# Omnicron_PCB.net
KiCad netlist of a schematic drawn in Altium Designer
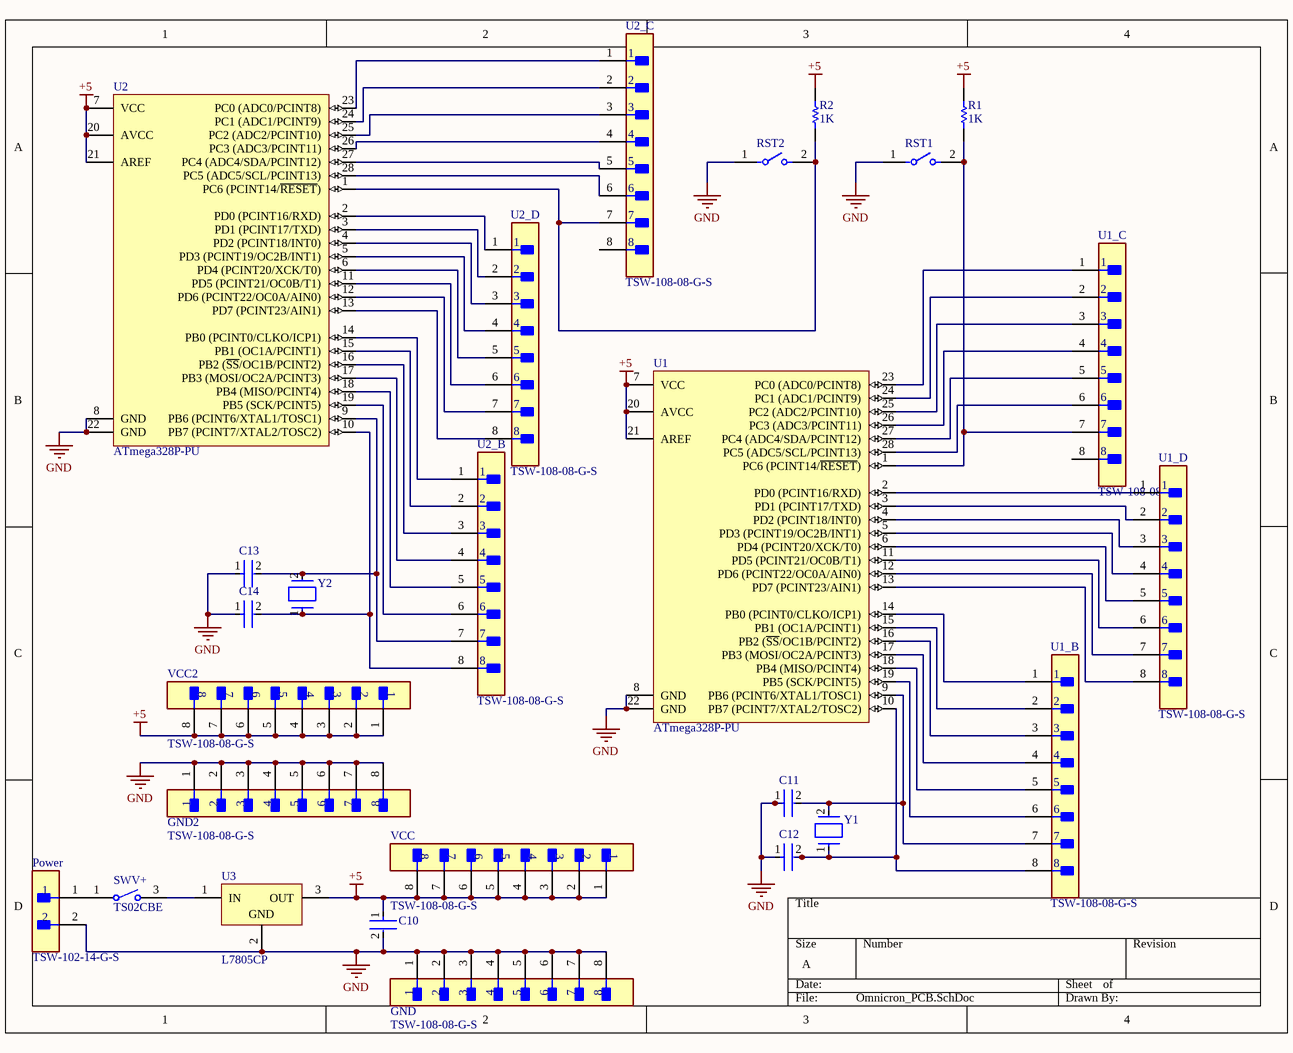
[diagram p0: Omnicron_PCB.SchDoc]

(export (version "E")
  (design (tool "Eeschema 10.0.6"))
  (components
    (comp (ref "C10")
      (value "~")
      (footprint "FP-561R10TSQ30-MFG")
      (description "CAP CER 30PF 1KV U2J RADIAL")
      (fields (field (name "TOLERANCE") "10%") (field (name "VOLTAGE") "1kV"))
      (libsource (lib "Altium Content Vault") (part "b4654b650e69147ec39a6b967a45e02"))
    )
    (comp (ref "C11")
      (value "~")
      (footprint "FP-561R10TSQ30-MFG")
      (description "CAP CER 30PF 1KV U2J RADIAL")
      (fields (field (name "TOLERANCE") "10%") (field (name "VOLTAGE") "1kV"))
      (libsource (lib "Altium Content Vault") (part "b4654b650e69147ec39a6b967a45e02"))
    )
    (comp (ref "C12")
      (value "~")
      (footprint "FP-561R10TSQ30-MFG")
      (description "CAP CER 30PF 1KV U2J RADIAL")
      (fields (field (name "TOLERANCE") "10%") (field (name "VOLTAGE") "1kV"))
      (libsource (lib "Altium Content Vault") (part "b4654b650e69147ec39a6b967a45e02"))
    )
    (comp (ref "C13")
      (value "~")
      (footprint "FP-561R10TSQ30-MFG")
      (description "CAP CER 30PF 1KV U2J RADIAL")
      (fields (field (name "TOLERANCE") "10%") (field (name "VOLTAGE") "1kV"))
      (libsource (lib "Altium Content Vault") (part "b4654b650e69147ec39a6b967a45e02"))
    )
    (comp (ref "C14")
      (value "~")
      (footprint "FP-561R10TSQ30-MFG")
      (description "CAP CER 30PF 1KV U2J RADIAL")
      (fields (field (name "TOLERANCE") "10%") (field (name "VOLTAGE") "1kV"))
      (libsource (lib "Altium Content Vault") (part "b4654b650e69147ec39a6b967a45e02"))
    )
    (comp (ref "GND")
      (value "TSW-108-08-G-S")
      (footprint "FP-TSW-108-08-G-S-MFG")
      (description "CONN HEADER VERT 8POS 2.54MM")
      (fields
        (field (name "MANUFACTURER") "Samtec")
        (field (name "OCTOPART") "https://octopart.com/tsw-108-08-g-s-samtec-272653")
      )
      (libsource (lib "") (part "99ec2b232beb5d2356d4d77f6a047f0_1"))
    )
    (comp (ref "GND2")
      (value "TSW-108-08-G-S")
      (footprint "FP-TSW-108-08-G-S-MFG")
      (description "CONN HEADER VERT 8POS 2.54MM")
      (fields
        (field (name "MANUFACTURER") "Samtec")
        (field (name "OCTOPART") "https://octopart.com/tsw-108-08-g-s-samtec-272653")
      )
      (libsource (lib "") (part "99ec2b232beb5d2356d4d77f6a047f0_1"))
    )
    (comp (ref "Power")
      (value "TSW-102-14-G-S")
      (footprint "FP-TSW-102-14-G-S-MFG")
      (description "CONN HEADER VERT 2POS 2.54MM")
      (libsource (lib "Altium Content Vault") (part "88c1139f9d239099ffebecbe3f7647a"))
    )
    (comp (ref "R1")
      (value "1K")
      (footprint "RESA60-630X240")
      (description "Axial Resistor, 1 KOhm, +/- 1%, 250 mW, -55 to 155 degC, 2-Pin THD, RoHS, Bulk")
      (fields (field (name "TOLERANCE") "1%"))
      (libsource (lib "Altium Content Vault") (part "RES-2"))
    )
    (comp (ref "R2")
      (value "1K")
      (footprint "RESA60-630X240")
      (description "Axial Resistor, 1 KOhm, +/- 1%, 250 mW, -55 to 155 degC, 2-Pin THD, RoHS, Bulk")
      (fields (field (name "TOLERANCE") "1%"))
      (libsource (lib "Altium Content Vault") (part "RES-2"))
    )
    (comp (ref "RST1")
      (value "~")
      (footprint "FP-FSM2JART-MFG")
      (description "SWITCH TACTILE SPST-NO 0.05A 12V")
      (libsource (lib "Altium Content Vault") (part "bb27bde45df87f1f469753f287ef5ae"))
    )
    (comp (ref "RST2")
      (value "~")
      (footprint "FP-FSM2JART-MFG")
      (description "SWITCH TACTILE SPST-NO 0.05A 12V")
      (libsource (lib "Altium Content Vault") (part "bb27bde45df87f1f469753f287ef5ae"))
    )
    (comp (ref "SWV+")
      (value "TS02CBE")
      (footprint "CKCP-TS02CBE_V")
      (description "Tiny Slide Switch, SPST, 20 V, -30 to 85 degC, 2-Pin THD, RoHS, Bulk")
      (fields (field (name "MANUFACTURER") "C&K Components"))
      (libsource (lib "Altium Content Vault") (part "SW-SPST-2"))
    )
    (comp (ref "U1")
      (value "ATmega328P-PU")
      (footprint "28P3")
      (libsource (lib "Altium Content Vault") (part "MC-8B-ATM48-IL28"))
    )
    (comp (ref "U1_B")
      (value "TSW-108-08-G-S")
      (footprint "FP-TSW-108-08-G-S-MFG")
      (description "CONN HEADER VERT 8POS 2.54MM")
      (fields
        (field (name "MANUFACTURER") "Samtec")
        (field (name "OCTOPART") "https://octopart.com/tsw-108-08-g-s-samtec-272653")
      )
      (libsource (lib "Altium Content Vault") (part "99ec2b232beb5d2356d4d77f6a047f0"))
    )
    (comp (ref "U1_C")
      (value "TSW-108-08-G-S")
      (footprint "FP-TSW-108-08-G-S-MFG")
      (description "CONN HEADER VERT 8POS 2.54MM")
      (fields
        (field (name "MANUFACTURER") "Samtec")
        (field (name "OCTOPART") "https://octopart.com/tsw-108-08-g-s-samtec-272653")
      )
      (libsource (lib "Altium Content Vault") (part "99ec2b232beb5d2356d4d77f6a047f0"))
    )
    (comp (ref "U1_D")
      (value "TSW-108-08-G-S")
      (footprint "FP-TSW-108-08-G-S-MFG")
      (description "CONN HEADER VERT 8POS 2.54MM")
      (fields
        (field (name "MANUFACTURER") "Samtec")
        (field (name "OCTOPART") "https://octopart.com/tsw-108-08-g-s-samtec-272653")
      )
      (libsource (lib "Altium Content Vault") (part "99ec2b232beb5d2356d4d77f6a047f0"))
    )
    (comp (ref "U2")
      (value "ATmega328P-PU")
      (footprint "28P3")
      (libsource (lib "Altium Content Vault") (part "MC-8B-ATM48-IL28"))
    )
    (comp (ref "U2_B")
      (value "TSW-108-08-G-S")
      (footprint "FP-TSW-108-08-G-S-MFG")
      (description "CONN HEADER VERT 8POS 2.54MM")
      (fields
        (field (name "MANUFACTURER") "Samtec")
        (field (name "OCTOPART") "https://octopart.com/tsw-108-08-g-s-samtec-272653")
      )
      (libsource (lib "Altium Content Vault") (part "99ec2b232beb5d2356d4d77f6a047f0"))
    )
    (comp (ref "U2_C")
      (value "TSW-108-08-G-S")
      (footprint "FP-TSW-108-08-G-S-MFG")
      (description "CONN HEADER VERT 8POS 2.54MM")
      (fields
        (field (name "MANUFACTURER") "Samtec")
        (field (name "OCTOPART") "https://octopart.com/tsw-108-08-g-s-samtec-272653")
      )
      (libsource (lib "Altium Content Vault") (part "99ec2b232beb5d2356d4d77f6a047f0"))
    )
    (comp (ref "U2_D")
      (value "TSW-108-08-G-S")
      (footprint "FP-TSW-108-08-G-S-MFG")
      (description "CONN HEADER VERT 8POS 2.54MM")
      (fields
        (field (name "MANUFACTURER") "Samtec")
        (field (name "OCTOPART") "https://octopart.com/tsw-108-08-g-s-samtec-272653")
      )
      (libsource (lib "Altium Content Vault") (part "99ec2b232beb5d2356d4d77f6a047f0"))
    )
    (comp (ref "U3")
      (value "L7805CP")
      (footprint "TO220FP")
      (description "Positive Voltage Regulator, 5V, 3-Pin TO-220FP")
      (libsource (lib "Altium Content Vault") (part "PM-REG-L4940-SIL3"))
    )
    (comp (ref "VCC")
      (value "TSW-108-08-G-S")
      (footprint "FP-TSW-108-08-G-S-MFG")
      (description "CONN HEADER VERT 8POS 2.54MM")
      (fields
        (field (name "MANUFACTURER") "Samtec")
        (field (name "OCTOPART") "https://octopart.com/tsw-108-08-g-s-samtec-272653")
      )
      (libsource (lib "Altium Content Vault") (part "99ec2b232beb5d2356d4d77f6a047f0"))
    )
    (comp (ref "VCC2")
      (value "TSW-108-08-G-S")
      (footprint "FP-TSW-108-08-G-S-MFG")
      (description "CONN HEADER VERT 8POS 2.54MM")
      (fields
        (field (name "MANUFACTURER") "Samtec")
        (field (name "OCTOPART") "https://octopart.com/tsw-108-08-g-s-samtec-272653")
      )
      (libsource (lib "Altium Content Vault") (part "99ec2b232beb5d2356d4d77f6a047f0"))
    )
    (comp (ref "Y1")
      (value "~")
      (footprint "FP-ECS-80-20-4X-MFG")
      (fields (field (name "TOLERANCE") "0.003%"))
      (libsource (lib "Altium Content Vault") (part "c23a69dc6c9e2f18f2079038eb95dd1"))
    )
    (comp (ref "Y2")
      (value "~")
      (footprint "FP-ECS-80-20-4X-MFG")
      (fields (field (name "TOLERANCE") "0.003%"))
      (libsource (lib "Altium Content Vault") (part "c23a69dc6c9e2f18f2079038eb95dd1"))
    )
  )
  (nets
    (net (code "1") (name "+5") (class "Default")
      (node (ref "C10") (pin "1") (pinfunction "1_1") (pintype "passive"))
      (node (ref "R1") (pin "1") (pinfunction "1_1") (pintype "passive"))
      (node (ref "R2") (pin "1") (pinfunction "1_1") (pintype "passive"))
      (node (ref "U1") (pin "20") (pinfunction "AVCC_20") (pintype "power_in"))
      (node (ref "U1") (pin "21") (pinfunction "AREF_21") (pintype "power_in"))
      (node (ref "U1") (pin "7") (pinfunction "VCC_7") (pintype "power_in"))
      (node (ref "U2") (pin "20") (pinfunction "AVCC_20") (pintype "power_in"))
      (node (ref "U2") (pin "21") (pinfunction "AREF_21") (pintype "power_in"))
      (node (ref "U2") (pin "7") (pinfunction "VCC_7") (pintype "power_in"))
      (node (ref "U3") (pin "3") (pinfunction "OUT_3") (pintype "power_in"))
      (node (ref "VCC") (pin "1") (pinfunction "1_1") (pintype "passive"))
      (node (ref "VCC") (pin "2") (pinfunction "2_2") (pintype "passive"))
      (node (ref "VCC") (pin "3") (pinfunction "3_3") (pintype "passive"))
      (node (ref "VCC") (pin "4") (pinfunction "4_4") (pintype "passive"))
      (node (ref "VCC") (pin "5") (pinfunction "5_5") (pintype "passive"))
      (node (ref "VCC") (pin "6") (pinfunction "6_6") (pintype "passive"))
      (node (ref "VCC") (pin "7") (pinfunction "7_7") (pintype "passive"))
      (node (ref "VCC") (pin "8") (pinfunction "8_8") (pintype "passive"))
      (node (ref "VCC2") (pin "1") (pinfunction "1_1") (pintype "passive"))
      (node (ref "VCC2") (pin "2") (pinfunction "2_2") (pintype "passive"))
      (node (ref "VCC2") (pin "3") (pinfunction "3_3") (pintype "passive"))
      (node (ref "VCC2") (pin "4") (pinfunction "4_4") (pintype "passive"))
      (node (ref "VCC2") (pin "5") (pinfunction "5_5") (pintype "passive"))
      (node (ref "VCC2") (pin "6") (pinfunction "6_6") (pintype "passive"))
      (node (ref "VCC2") (pin "7") (pinfunction "7_7") (pintype "passive"))
      (node (ref "VCC2") (pin "8") (pinfunction "8_8") (pintype "passive"))
    )
    (net (code "2") (name "GND") (class "Default")
      (node (ref "C10") (pin "2") (pinfunction "2_2") (pintype "passive"))
      (node (ref "C11") (pin "1") (pinfunction "1_1") (pintype "passive"))
      (node (ref "C12") (pin "1") (pinfunction "1_1") (pintype "passive"))
      (node (ref "C13") (pin "1") (pinfunction "1_1") (pintype "passive"))
      (node (ref "C14") (pin "1") (pinfunction "1_1") (pintype "passive"))
      (node (ref "GND") (pin "1") (pinfunction "1_1") (pintype "passive"))
      (node (ref "GND") (pin "2") (pinfunction "2_2") (pintype "passive"))
      (node (ref "GND") (pin "3") (pinfunction "3_3") (pintype "passive"))
      (node (ref "GND") (pin "4") (pinfunction "4_4") (pintype "passive"))
      (node (ref "GND") (pin "5") (pinfunction "5_5") (pintype "passive"))
      (node (ref "GND") (pin "6") (pinfunction "6_6") (pintype "passive"))
      (node (ref "GND") (pin "7") (pinfunction "7_7") (pintype "passive"))
      (node (ref "GND") (pin "8") (pinfunction "8_8") (pintype "passive"))
      (node (ref "GND2") (pin "1") (pinfunction "1_1") (pintype "passive"))
      (node (ref "GND2") (pin "2") (pinfunction "2_2") (pintype "passive"))
      (node (ref "GND2") (pin "3") (pinfunction "3_3") (pintype "passive"))
      (node (ref "GND2") (pin "4") (pinfunction "4_4") (pintype "passive"))
      (node (ref "GND2") (pin "5") (pinfunction "5_5") (pintype "passive"))
      (node (ref "GND2") (pin "6") (pinfunction "6_6") (pintype "passive"))
      (node (ref "GND2") (pin "7") (pinfunction "7_7") (pintype "passive"))
      (node (ref "GND2") (pin "8") (pinfunction "8_8") (pintype "passive"))
      (node (ref "Power") (pin "2") (pinfunction "2_2") (pintype "passive"))
      (node (ref "RST1") (pin "1") (pinfunction "1_1") (pintype "passive"))
      (node (ref "RST2") (pin "1") (pinfunction "1_1") (pintype "passive"))
      (node (ref "U1") (pin "22") (pinfunction "GND_22") (pintype "power_in"))
      (node (ref "U1") (pin "8") (pinfunction "GND_8") (pintype "power_in"))
      (node (ref "U2") (pin "22") (pinfunction "GND_22") (pintype "power_in"))
      (node (ref "U2") (pin "8") (pinfunction "GND_8") (pintype "power_in"))
      (node (ref "U3") (pin "2") (pinfunction "GND_2") (pintype "power_in"))
    )
    (net (code "3") (name "Net-(Power-Pad1)") (class "Default")
      (node (ref "Power") (pin "1") (pinfunction "1_1") (pintype "passive"))
      (node (ref "SWV+") (pin "1") (pinfunction "1_1") (pintype "passive"))
    )
    (net (code "4") (name "Net-(U1-PB0_(PCINT0{slash}CLKO{slash}ICP1))") (class "Default")
      (node (ref "U1") (pin "14") (pinfunction "PB0_(PCINT0/CLKO/ICP1)_14") (pintype "bidirectional"))
      (node (ref "U1_B") (pin "1") (pinfunction "1_1") (pintype "passive"))
    )
    (net (code "5") (name "Net-(U1-PB1_(OC1A{slash}PCINT1))") (class "Default")
      (node (ref "U1") (pin "15") (pinfunction "PB1_(OC1A/PCINT1)_15") (pintype "bidirectional"))
      (node (ref "U1_B") (pin "2") (pinfunction "2_2") (pintype "passive"))
    )
    (net (code "6") (name "Net-(U1-PB2_(~{SS}{slash}OC1B{slash}PCINT2))") (class "Default")
      (node (ref "U1") (pin "16") (pinfunction "PB2_(~{SS}/OC1B/PCINT2)_16") (pintype "bidirectional"))
      (node (ref "U1_B") (pin "3") (pinfunction "3_3") (pintype "passive"))
    )
    (net (code "7") (name "Net-(U1-PB3_(MOSI{slash}OC2A{slash}PCINT3))") (class "Default")
      (node (ref "U1") (pin "17") (pinfunction "PB3_(MOSI/OC2A/PCINT3)_17") (pintype "bidirectional"))
      (node (ref "U1_B") (pin "4") (pinfunction "4_4") (pintype "passive"))
    )
    (net (code "8") (name "Net-(U1-PB4_(MISO{slash}PCINT4))") (class "Default")
      (node (ref "U1") (pin "18") (pinfunction "PB4_(MISO/PCINT4)_18") (pintype "bidirectional"))
      (node (ref "U1_B") (pin "5") (pinfunction "5_5") (pintype "passive"))
    )
    (net (code "9") (name "Net-(U1-PB5_(SCK{slash}PCINT5))") (class "Default")
      (node (ref "U1") (pin "19") (pinfunction "PB5_(SCK/PCINT5)_19") (pintype "bidirectional"))
      (node (ref "U1_B") (pin "6") (pinfunction "6_6") (pintype "passive"))
    )
    (net (code "10") (name "Net-(U1-PB6_(PCINT6{slash}XTAL1{slash}TOSC1))") (class "Default")
      (node (ref "C11") (pin "2") (pinfunction "2_2") (pintype "passive"))
      (node (ref "U1") (pin "9") (pinfunction "PB6_(PCINT6/XTAL1/TOSC1)_9") (pintype "bidirectional"))
      (node (ref "U1_B") (pin "7") (pinfunction "7_7") (pintype "passive"))
      (node (ref "Y1") (pin "2") (pinfunction "2_2") (pintype "passive"))
    )
    (net (code "11") (name "Net-(U1-PB7_(PCINT7{slash}XTAL2{slash}TOSC2))") (class "Default")
      (node (ref "C12") (pin "2") (pinfunction "2_2") (pintype "passive"))
      (node (ref "U1") (pin "10") (pinfunction "PB7_(PCINT7/XTAL2/TOSC2)_10") (pintype "bidirectional"))
      (node (ref "U1_B") (pin "8") (pinfunction "8_8") (pintype "passive"))
      (node (ref "Y1") (pin "1") (pinfunction "1_1") (pintype "passive"))
    )
    (net (code "12") (name "Net-(U1-PC0_(ADC0{slash}PCINT8))") (class "Default")
      (node (ref "U1") (pin "23") (pinfunction "PC0_(ADC0/PCINT8)_23") (pintype "bidirectional"))
      (node (ref "U1_C") (pin "1") (pinfunction "1_1") (pintype "passive"))
    )
    (net (code "13") (name "Net-(U1-PC1_(ADC1{slash}PCINT9))") (class "Default")
      (node (ref "U1") (pin "24") (pinfunction "PC1_(ADC1/PCINT9)_24") (pintype "bidirectional"))
      (node (ref "U1_C") (pin "2") (pinfunction "2_2") (pintype "passive"))
    )
    (net (code "14") (name "Net-(U1-PC2_(ADC2{slash}PCINT10))") (class "Default")
      (node (ref "U1") (pin "25") (pinfunction "PC2_(ADC2/PCINT10)_25") (pintype "bidirectional"))
      (node (ref "U1_C") (pin "3") (pinfunction "3_3") (pintype "passive"))
    )
    (net (code "15") (name "Net-(U1-PC3_(ADC3{slash}PCINT11))") (class "Default")
      (node (ref "U1") (pin "26") (pinfunction "PC3_(ADC3/PCINT11)_26") (pintype "bidirectional"))
      (node (ref "U1_C") (pin "4") (pinfunction "4_4") (pintype "passive"))
    )
    (net (code "16") (name "Net-(U1-PC4_(ADC4{slash}SDA{slash}PCINT12))") (class "Default")
      (node (ref "U1") (pin "27") (pinfunction "PC4_(ADC4/SDA/PCINT12)_27") (pintype "bidirectional"))
      (node (ref "U1_C") (pin "5") (pinfunction "5_5") (pintype "passive"))
    )
    (net (code "17") (name "Net-(U1-PC5_(ADC5{slash}SCL{slash}PCINT13))") (class "Default")
      (node (ref "U1") (pin "28") (pinfunction "PC5_(ADC5/SCL/PCINT13)_28") (pintype "bidirectional"))
      (node (ref "U1_C") (pin "6") (pinfunction "6_6") (pintype "passive"))
    )
    (net (code "18") (name "Net-(U1-PC6_(PCINT14{slash}~{RESET}))") (class "Default")
      (node (ref "R1") (pin "2") (pinfunction "2_2") (pintype "passive"))
      (node (ref "RST1") (pin "2") (pinfunction "2_2") (pintype "passive"))
      (node (ref "U1") (pin "1") (pinfunction "PC6_(PCINT14/~{RESET})_1") (pintype "bidirectional"))
      (node (ref "U1_C") (pin "7") (pinfunction "7_7") (pintype "passive"))
    )
    (net (code "19") (name "Net-(U1-PD0_(PCINT16{slash}RXD))") (class "Default")
      (node (ref "U1") (pin "2") (pinfunction "PD0_(PCINT16/RXD)_2") (pintype "bidirectional"))
      (node (ref "U1_D") (pin "1") (pinfunction "1_1") (pintype "passive"))
    )
    (net (code "20") (name "Net-(U1-PD1_(PCINT17{slash}TXD))") (class "Default")
      (node (ref "U1") (pin "3") (pinfunction "PD1_(PCINT17/TXD)_3") (pintype "bidirectional"))
      (node (ref "U1_D") (pin "2") (pinfunction "2_2") (pintype "passive"))
    )
    (net (code "21") (name "Net-(U1-PD2_(PCINT18{slash}INT0))") (class "Default")
      (node (ref "U1") (pin "4") (pinfunction "PD2_(PCINT18/INT0)_4") (pintype "bidirectional"))
      (node (ref "U1_D") (pin "3") (pinfunction "3_3") (pintype "passive"))
    )
    (net (code "22") (name "Net-(U1-PD3_(PCINT19{slash}OC2B{slash}INT1))") (class "Default")
      (node (ref "U1") (pin "5") (pinfunction "PD3_(PCINT19/OC2B/INT1)_5") (pintype "bidirectional"))
      (node (ref "U1_D") (pin "4") (pinfunction "4_4") (pintype "passive"))
    )
    (net (code "23") (name "Net-(U1-PD4_(PCINT20{slash}XCK{slash}T0))") (class "Default")
      (node (ref "U1") (pin "6") (pinfunction "PD4_(PCINT20/XCK/T0)_6") (pintype "bidirectional"))
      (node (ref "U1_D") (pin "5") (pinfunction "5_5") (pintype "passive"))
    )
    (net (code "24") (name "Net-(U1-PD5_(PCINT21{slash}OC0B{slash}T1))") (class "Default")
      (node (ref "U1") (pin "11") (pinfunction "PD5_(PCINT21/OC0B/T1)_11") (pintype "bidirectional"))
      (node (ref "U1_D") (pin "6") (pinfunction "6_6") (pintype "passive"))
    )
    (net (code "25") (name "Net-(U1-PD6_(PCINT22{slash}OC0A{slash}AIN0))") (class "Default")
      (node (ref "U1") (pin "12") (pinfunction "PD6_(PCINT22/OC0A/AIN0)_12") (pintype "bidirectional"))
      (node (ref "U1_D") (pin "7") (pinfunction "7_7") (pintype "passive"))
    )
    (net (code "26") (name "Net-(U1-PD7_(PCINT23{slash}AIN1))") (class "Default")
      (node (ref "U1") (pin "13") (pinfunction "PD7_(PCINT23/AIN1)_13") (pintype "bidirectional"))
      (node (ref "U1_D") (pin "8") (pinfunction "8_8") (pintype "passive"))
    )
    (net (code "27") (name "Net-(U2-PB0_(PCINT0{slash}CLKO{slash}ICP1))") (class "Default")
      (node (ref "U2") (pin "14") (pinfunction "PB0_(PCINT0/CLKO/ICP1)_14") (pintype "bidirectional"))
      (node (ref "U2_B") (pin "1") (pinfunction "1_1") (pintype "passive"))
    )
    (net (code "28") (name "Net-(U2-PB1_(OC1A{slash}PCINT1))") (class "Default")
      (node (ref "U2") (pin "15") (pinfunction "PB1_(OC1A/PCINT1)_15") (pintype "bidirectional"))
      (node (ref "U2_B") (pin "2") (pinfunction "2_2") (pintype "passive"))
    )
    (net (code "29") (name "Net-(U2-PB2_(~{SS}{slash}OC1B{slash}PCINT2))") (class "Default")
      (node (ref "U2") (pin "16") (pinfunction "PB2_(~{SS}/OC1B/PCINT2)_16") (pintype "bidirectional"))
      (node (ref "U2_B") (pin "3") (pinfunction "3_3") (pintype "passive"))
    )
    (net (code "30") (name "Net-(U2-PB3_(MOSI{slash}OC2A{slash}PCINT3))") (class "Default")
      (node (ref "U2") (pin "17") (pinfunction "PB3_(MOSI/OC2A/PCINT3)_17") (pintype "bidirectional"))
      (node (ref "U2_B") (pin "4") (pinfunction "4_4") (pintype "passive"))
    )
    (net (code "31") (name "Net-(U2-PB4_(MISO{slash}PCINT4))") (class "Default")
      (node (ref "U2") (pin "18") (pinfunction "PB4_(MISO/PCINT4)_18") (pintype "bidirectional"))
      (node (ref "U2_B") (pin "5") (pinfunction "5_5") (pintype "passive"))
    )
    (net (code "32") (name "Net-(U2-PB5_(SCK{slash}PCINT5))") (class "Default")
      (node (ref "U2") (pin "19") (pinfunction "PB5_(SCK/PCINT5)_19") (pintype "bidirectional"))
      (node (ref "U2_B") (pin "6") (pinfunction "6_6") (pintype "passive"))
    )
    (net (code "33") (name "Net-(U2-PB6_(PCINT6{slash}XTAL1{slash}TOSC1))") (class "Default")
      (node (ref "C13") (pin "2") (pinfunction "2_2") (pintype "passive"))
      (node (ref "U2") (pin "9") (pinfunction "PB6_(PCINT6/XTAL1/TOSC1)_9") (pintype "bidirectional"))
      (node (ref "U2_B") (pin "7") (pinfunction "7_7") (pintype "passive"))
      (node (ref "Y2") (pin "2") (pinfunction "2_2") (pintype "passive"))
    )
    (net (code "34") (name "Net-(U2-PB7_(PCINT7{slash}XTAL2{slash}TOSC2))") (class "Default")
      (node (ref "C14") (pin "2") (pinfunction "2_2") (pintype "passive"))
      (node (ref "U2") (pin "10") (pinfunction "PB7_(PCINT7/XTAL2/TOSC2)_10") (pintype "bidirectional"))
      (node (ref "U2_B") (pin "8") (pinfunction "8_8") (pintype "passive"))
      (node (ref "Y2") (pin "1") (pinfunction "1_1") (pintype "passive"))
    )
    (net (code "35") (name "Net-(U2-PC0_(ADC0{slash}PCINT8))") (class "Default")
      (node (ref "U2") (pin "23") (pinfunction "PC0_(ADC0/PCINT8)_23") (pintype "bidirectional"))
      (node (ref "U2_C") (pin "1") (pinfunction "1_1") (pintype "passive"))
    )
    (net (code "36") (name "Net-(U2-PC1_(ADC1{slash}PCINT9))") (class "Default")
      (node (ref "U2") (pin "24") (pinfunction "PC1_(ADC1/PCINT9)_24") (pintype "bidirectional"))
      (node (ref "U2_C") (pin "2") (pinfunction "2_2") (pintype "passive"))
    )
    (net (code "37") (name "Net-(U2-PC2_(ADC2{slash}PCINT10))") (class "Default")
      (node (ref "U2") (pin "25") (pinfunction "PC2_(ADC2/PCINT10)_25") (pintype "bidirectional"))
      (node (ref "U2_C") (pin "3") (pinfunction "3_3") (pintype "passive"))
    )
    (net (code "38") (name "Net-(U2-PC3_(ADC3{slash}PCINT11))") (class "Default")
      (node (ref "U2") (pin "26") (pinfunction "PC3_(ADC3/PCINT11)_26") (pintype "bidirectional"))
      (node (ref "U2_C") (pin "4") (pinfunction "4_4") (pintype "passive"))
    )
    (net (code "39") (name "Net-(U2-PC4_(ADC4{slash}SDA{slash}PCINT12))") (class "Default")
      (node (ref "U2") (pin "27") (pinfunction "PC4_(ADC4/SDA/PCINT12)_27") (pintype "bidirectional"))
      (node (ref "U2_C") (pin "5") (pinfunction "5_5") (pintype "passive"))
    )
    (net (code "40") (name "Net-(U2-PC5_(ADC5{slash}SCL{slash}PCINT13))") (class "Default")
      (node (ref "U2") (pin "28") (pinfunction "PC5_(ADC5/SCL/PCINT13)_28") (pintype "bidirectional"))
      (node (ref "U2_C") (pin "6") (pinfunction "6_6") (pintype "passive"))
    )
    (net (code "41") (name "Net-(U2-PC6_(PCINT14{slash}~{RESET}))") (class "Default")
      (node (ref "R2") (pin "2") (pinfunction "2_2") (pintype "passive"))
      (node (ref "RST2") (pin "2") (pinfunction "2_2") (pintype "passive"))
      (node (ref "U2") (pin "1") (pinfunction "PC6_(PCINT14/~{RESET})_1") (pintype "bidirectional"))
      (node (ref "U2_C") (pin "7") (pinfunction "7_7") (pintype "passive"))
    )
    (net (code "42") (name "Net-(U2-PD0_(PCINT16{slash}RXD))") (class "Default")
      (node (ref "U2") (pin "2") (pinfunction "PD0_(PCINT16/RXD)_2") (pintype "bidirectional"))
      (node (ref "U2_D") (pin "1") (pinfunction "1_1") (pintype "passive"))
    )
    (net (code "43") (name "Net-(U2-PD1_(PCINT17{slash}TXD))") (class "Default")
      (node (ref "U2") (pin "3") (pinfunction "PD1_(PCINT17/TXD)_3") (pintype "bidirectional"))
      (node (ref "U2_D") (pin "2") (pinfunction "2_2") (pintype "passive"))
    )
    (net (code "44") (name "Net-(U2-PD2_(PCINT18{slash}INT0))") (class "Default")
      (node (ref "U2") (pin "4") (pinfunction "PD2_(PCINT18/INT0)_4") (pintype "bidirectional"))
      (node (ref "U2_D") (pin "3") (pinfunction "3_3") (pintype "passive"))
    )
    (net (code "45") (name "Net-(U2-PD3_(PCINT19{slash}OC2B{slash}INT1))") (class "Default")
      (node (ref "U2") (pin "5") (pinfunction "PD3_(PCINT19/OC2B/INT1)_5") (pintype "bidirectional"))
      (node (ref "U2_D") (pin "4") (pinfunction "4_4") (pintype "passive"))
    )
    (net (code "46") (name "Net-(U2-PD4_(PCINT20{slash}XCK{slash}T0))") (class "Default")
      (node (ref "U2") (pin "6") (pinfunction "PD4_(PCINT20/XCK/T0)_6") (pintype "bidirectional"))
      (node (ref "U2_D") (pin "5") (pinfunction "5_5") (pintype "passive"))
    )
    (net (code "47") (name "Net-(U2-PD5_(PCINT21{slash}OC0B{slash}T1))") (class "Default")
      (node (ref "U2") (pin "11") (pinfunction "PD5_(PCINT21/OC0B/T1)_11") (pintype "bidirectional"))
      (node (ref "U2_D") (pin "6") (pinfunction "6_6") (pintype "passive"))
    )
    (net (code "48") (name "Net-(U2-PD6_(PCINT22{slash}OC0A{slash}AIN0))") (class "Default")
      (node (ref "U2") (pin "12") (pinfunction "PD6_(PCINT22/OC0A/AIN0)_12") (pintype "bidirectional"))
      (node (ref "U2_D") (pin "7") (pinfunction "7_7") (pintype "passive"))
    )
    (net (code "49") (name "Net-(U2-PD7_(PCINT23{slash}AIN1))") (class "Default")
      (node (ref "U2") (pin "13") (pinfunction "PD7_(PCINT23/AIN1)_13") (pintype "bidirectional"))
      (node (ref "U2_D") (pin "8") (pinfunction "8_8") (pintype "passive"))
    )
    (net (code "50") (name "Net-(U3-IN)") (class "Default")
      (node (ref "SWV+") (pin "3") (pinfunction "3_3") (pintype "passive"))
      (node (ref "U3") (pin "1") (pinfunction "IN_1") (pintype "power_in"))
    )
    (net (code "51") (name "unconnected-(U1_C-Pad8)") (class "Default")
      (node (ref "U1_C") (pin "8") (pinfunction "8_8") (pintype "passive"))
    )
    (net (code "52") (name "unconnected-(U2_C-Pad8)") (class "Default")
      (node (ref "U2_C") (pin "8") (pinfunction "8_8") (pintype "passive"))
    )
  )
)
